# LilyPad_Slide_Switch.net
KiCad netlist of a schematic drawn in EAGLE
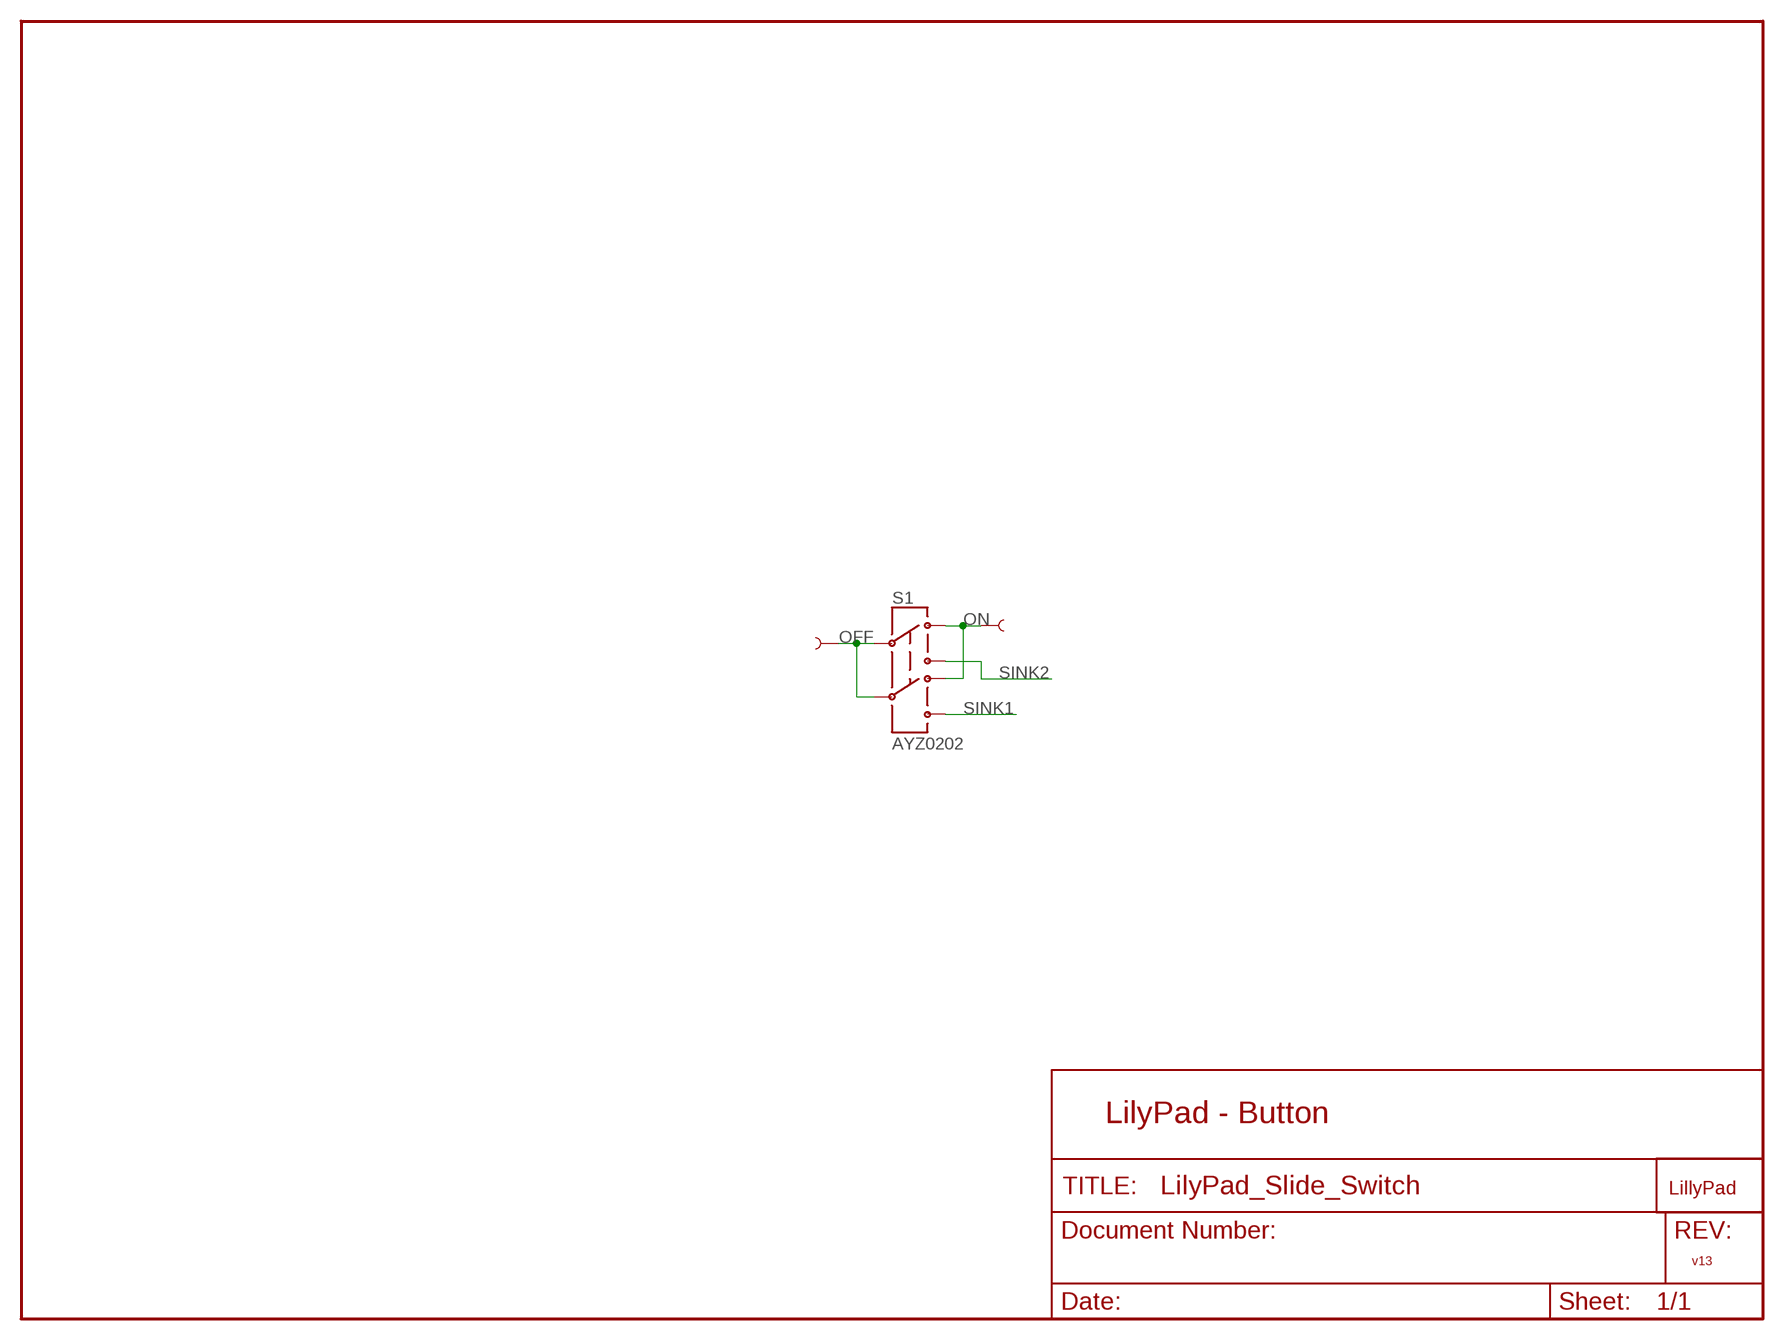
[diagram p0: schematic, sheet 1]

(export (version "E")
  (design (tool "Eeschema 10.0.6"))
  (components
    (comp (ref "LOGO1")
      (value "LOGO-LPL")
      (footprint "eagle-import:LOGO-L")
      (libsource (lib "eagle-import") (part "LOGO-LPL"))
    )
    (comp (ref "S1")
      (value "AYZ0202")
      (footprint "eagle-import:AYZ0202")
      (libsource (lib "eagle-import") (part "AYZ0202"))
    )
    (comp (ref "SLIDEOFF")
      (value "SEWTAP8")
      (footprint "eagle-import:PETAL-MEDIUM-2SIDE")
      (libsource (lib "eagle-import") (part "SEWTAP8"))
    )
    (comp (ref "SLIDEON")
      (value "SEWTAP8")
      (footprint "eagle-import:PETAL-MEDIUM-2SIDE")
      (libsource (lib "eagle-import") (part "SEWTAP8"))
    )
  )
  (nets
    (net (code "1") (name "/OFF") (class "Default")
      (node (ref "S1") (pin "2") (pinfunction "2_2") (pintype "bidirectional"))
      (node (ref "S1") (pin "5") (pinfunction "5_5") (pintype "bidirectional"))
      (node (ref "SLIDEOFF") (pin "1") (pinfunction "1_1") (pintype "bidirectional"))
    )
    (net (code "2") (name "/ON") (class "Default")
      (node (ref "S1") (pin "3") (pinfunction "1_3") (pintype "bidirectional"))
      (node (ref "S1") (pin "6") (pinfunction "4_6") (pintype "bidirectional"))
      (node (ref "SLIDEON") (pin "1") (pinfunction "1_1") (pintype "bidirectional"))
    )
    (net (code "3") (name "/SINK1") (class "Default")
      (node (ref "S1") (pin "4") (pinfunction "6_4") (pintype "bidirectional"))
    )
    (net (code "4") (name "/SINK2") (class "Default")
      (node (ref "S1") (pin "1") (pinfunction "3_1") (pintype "bidirectional"))
    )
  )
)
